# smart-home_matherboard.net
KiCad netlist of a schematic drawn in EAGLE
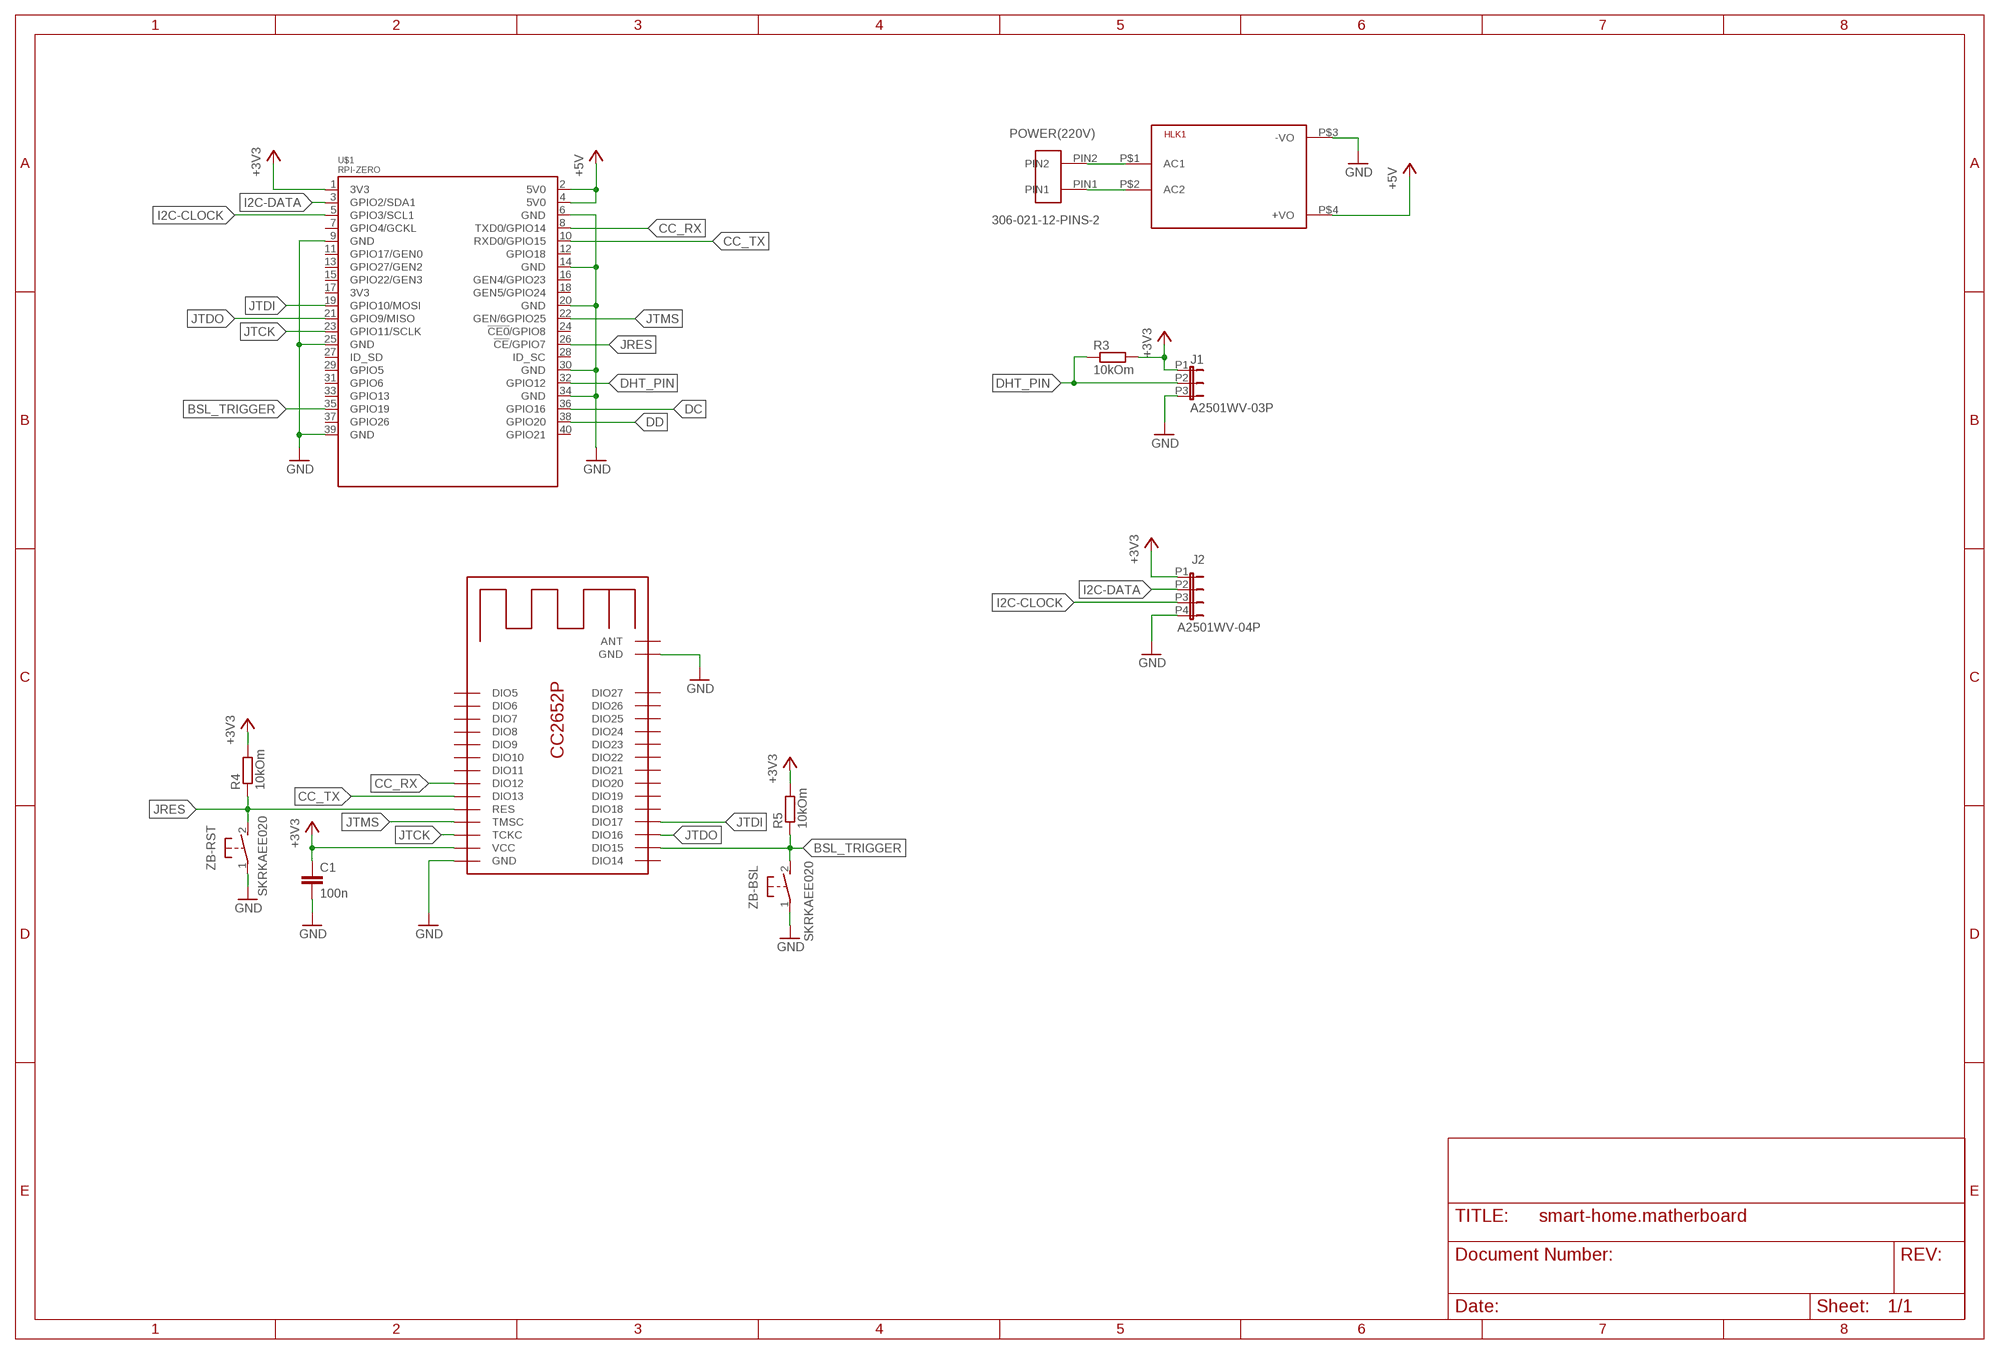
[diagram p0: schematic, sheet 1]

(export (version "E")
  (design (tool "Eeschema 10.0.6"))
  (components
    (comp (ref "C1")
      (value "100n")
      (footprint "eagle-import:C0603K")
      (libsource (lib "eagle-import") (part "C-EUC0603K"))
    )
    (comp (ref "HLK1")
      (value "HLK-PM013W")
      (footprint "eagle-import:HLK-PM01")
      (libsource (lib "eagle-import") (part "HLK-PM013W"))
    )
    (comp (ref "J1")
      (value "A2501WV-03P")
      (footprint "eagle-import:A2501WV-03P")
      (libsource (lib "eagle-import") (part "A2501WV-03P"))
    )
    (comp (ref "J2")
      (value "A2501WV-04P")
      (footprint "eagle-import:A2501WV-04P")
      (libsource (lib "eagle-import") (part "A2501WV-04P"))
    )
    (comp (ref "POWER(220V)")
      (value "306-021-12-PINS-2")
      (footprint "eagle-import:SERIA-306-2PIN")
      (libsource (lib "eagle-import") (part "306-021-12-PINS-2"))
    )
    (comp (ref "R3")
      (value "10kOm")
      (footprint "eagle-import:R0603")
      (libsource (lib "eagle-import") (part "R-EU_R0603"))
    )
    (comp (ref "R4")
      (value "10kOm")
      (footprint "eagle-import:R0603")
      (libsource (lib "eagle-import") (part "R-EU_R0603"))
    )
    (comp (ref "R5")
      (value "10kOm")
      (footprint "eagle-import:R0603")
      (libsource (lib "eagle-import") (part "R-EU_R0603"))
    )
    (comp (ref "U$1")
      (value "RPI-ZERO")
      (footprint "eagle-import:RASPBERRYPI_BASTELSTUBE_V13_RASPI_BOARD_B+_FULL")
      (libsource (lib "eagle-import") (part "RPI-ZERO"))
    )
    (comp (ref "U1")
      (value "CC2652P2-DUOWEISI")
      (footprint "eagle-import:CC2653P2-DUOWEISI")
      (libsource (lib "eagle-import") (part "CC2652P2-DUOWEISI"))
    )
    (comp (ref "ZB-BSL")
      (value "SKRKAEE020")
      (footprint "eagle-import:SKRKAEE020")
      (libsource (lib "eagle-import") (part "SKRKAEE020"))
    )
    (comp (ref "ZB-RST")
      (value "SKRKAEE020")
      (footprint "eagle-import:SKRKAEE020")
      (libsource (lib "eagle-import") (part "SKRKAEE020"))
    )
  )
  (nets
    (net (code "1") (name "+3V3") (class "Default")
      (node (ref "C1") (pin "1") (pinfunction "1_1") (pintype "passive"))
      (node (ref "J1") (pin "P1") (pinfunction "1_P1") (pintype "passive"))
      (node (ref "J2") (pin "P1") (pinfunction "1_P1") (pintype "passive"))
      (node (ref "R3") (pin "2") (pinfunction "2_2") (pintype "passive"))
      (node (ref "R4") (pin "2") (pinfunction "2_2") (pintype "passive"))
      (node (ref "R5") (pin "2") (pinfunction "2_2") (pintype "passive"))
      (node (ref "U$1") (pin "1") (pinfunction "3V3_1") (pintype "power_in"))
      (node (ref "U1") (pin "VCC") (pinfunction "VCC_VCC") (pintype "bidirectional"))
    )
    (net (code "2") (name "+5V") (class "Default")
      (node (ref "HLK1") (pin "P$4") (pinfunction "+VO_P$4") (pintype "bidirectional"))
      (node (ref "U$1") (pin "2") (pinfunction "5V0_2") (pintype "power_in"))
      (node (ref "U$1") (pin "4") (pinfunction "5V0_4") (pintype "power_in"))
    )
    (net (code "3") (name "/3V3") (class "Default")
      (node (ref "U$1") (pin "17") (pinfunction "3V3_17") (pintype "power_in"))
    )
    (net (code "4") (name "BSL_TRIGGER") (class "Default")
      (node (ref "R5") (pin "1") (pinfunction "1_1") (pintype "passive"))
      (node (ref "U$1") (pin "35") (pinfunction "GPIO19_35") (pintype "bidirectional"))
      (node (ref "U1") (pin "DIO15") (pinfunction "DIO15_DIO15") (pintype "bidirectional"))
      (node (ref "ZB-BSL") (pin "2") (pinfunction "2_2") (pintype "passive"))
    )
    (net (code "5") (name "CC_RX") (class "Default")
      (node (ref "U$1") (pin "8") (pinfunction "TXD0/GPIO14_8") (pintype "bidirectional"))
      (node (ref "U1") (pin "DIO12") (pinfunction "DIO12_DIO12") (pintype "bidirectional"))
    )
    (net (code "6") (name "CC_TX") (class "Default")
      (node (ref "U$1") (pin "10") (pinfunction "RXD0/GPIO15_10") (pintype "bidirectional"))
      (node (ref "U1") (pin "DIO13") (pinfunction "DIO13_DIO13") (pintype "bidirectional"))
    )
    (net (code "7") (name "DC") (class "Default")
      (node (ref "U$1") (pin "36") (pinfunction "GPIO16_36") (pintype "bidirectional"))
    )
    (net (code "8") (name "DD") (class "Default")
      (node (ref "U$1") (pin "38") (pinfunction "GPIO20_38") (pintype "bidirectional"))
    )
    (net (code "9") (name "DHT_PIN") (class "Default")
      (node (ref "J1") (pin "P2") (pinfunction "2_P2") (pintype "passive"))
      (node (ref "R3") (pin "1") (pinfunction "1_1") (pintype "passive"))
      (node (ref "U$1") (pin "32") (pinfunction "GPIO12_32") (pintype "bidirectional"))
    )
    (net (code "10") (name "GND") (class "Default")
      (node (ref "C1") (pin "2") (pinfunction "2_2") (pintype "passive"))
      (node (ref "HLK1") (pin "P$3") (pinfunction "-VO_P$3") (pintype "bidirectional"))
      (node (ref "J1") (pin "P3") (pinfunction "3_P3") (pintype "passive"))
      (node (ref "J2") (pin "P4") (pinfunction "4_P4") (pintype "passive"))
      (node (ref "U$1") (pin "14") (pinfunction "GND_14") (pintype "power_in"))
      (node (ref "U$1") (pin "20") (pinfunction "GND_20") (pintype "power_in"))
      (node (ref "U$1") (pin "25") (pinfunction "GND_25") (pintype "power_in"))
      (node (ref "U$1") (pin "30") (pinfunction "GND_30") (pintype "power_in"))
      (node (ref "U$1") (pin "34") (pinfunction "GND_34") (pintype "power_in"))
      (node (ref "U$1") (pin "39") (pinfunction "GND_39") (pintype "power_in"))
      (node (ref "U$1") (pin "6") (pinfunction "GND_6") (pintype "power_in"))
      (node (ref "U$1") (pin "9") (pinfunction "GND_9") (pintype "power_in"))
      (node (ref "U1") (pin "GND") (pinfunction "GND_GND") (pintype "bidirectional"))
      (node (ref "U1") (pin "GND@1") (pinfunction "GND_GND@1") (pintype "bidirectional"))
      (node (ref "ZB-BSL") (pin "1") (pinfunction "1_1") (pintype "passive"))
      (node (ref "ZB-RST") (pin "1") (pinfunction "1_1") (pintype "passive"))
    )
    (net (code "11") (name "I2C-CLOCK") (class "Default")
      (node (ref "J2") (pin "P3") (pinfunction "3_P3") (pintype "passive"))
      (node (ref "U$1") (pin "5") (pinfunction "GPIO3/SCL1_5") (pintype "bidirectional"))
    )
    (net (code "12") (name "I2C-DATA") (class "Default")
      (node (ref "J2") (pin "P2") (pinfunction "2_P2") (pintype "passive"))
      (node (ref "U$1") (pin "3") (pinfunction "GPIO2/SDA1_3") (pintype "bidirectional"))
    )
    (net (code "13") (name "JRES") (class "Default")
      (node (ref "R4") (pin "1") (pinfunction "1_1") (pintype "passive"))
      (node (ref "U$1") (pin "26") (pinfunction "~{CE}/GPIO7_26") (pintype "bidirectional"))
      (node (ref "U1") (pin "RES") (pinfunction "RES_RES") (pintype "bidirectional"))
      (node (ref "ZB-RST") (pin "2") (pinfunction "2_2") (pintype "passive"))
    )
    (net (code "14") (name "JTCK") (class "Default")
      (node (ref "U$1") (pin "23") (pinfunction "GPIO11/SCLK_23") (pintype "bidirectional"))
      (node (ref "U1") (pin "TCKC") (pinfunction "TCKC_TCKC") (pintype "bidirectional"))
    )
    (net (code "15") (name "JTDI") (class "Default")
      (node (ref "U$1") (pin "19") (pinfunction "GPIO10/MOSI_19") (pintype "bidirectional"))
      (node (ref "U1") (pin "DIO17") (pinfunction "DIO17_DIO17") (pintype "bidirectional"))
    )
    (net (code "16") (name "JTDO") (class "Default")
      (node (ref "U$1") (pin "21") (pinfunction "GPIO9/MISO_21") (pintype "bidirectional"))
      (node (ref "U1") (pin "DIO16") (pinfunction "DIO16_DIO16") (pintype "bidirectional"))
    )
    (net (code "17") (name "JTMS") (class "Default")
      (node (ref "U$1") (pin "22") (pinfunction "GEN/6GPIO25_22") (pintype "bidirectional"))
      (node (ref "U1") (pin "TMSC") (pinfunction "TMSC_TMSC") (pintype "bidirectional"))
    )
    (net (code "18") (name "Net-(HLK1-AC1)") (class "Default")
      (node (ref "HLK1") (pin "P$1") (pinfunction "AC1_P$1") (pintype "bidirectional"))
      (node (ref "POWER(220V)") (pin "PIN2") (pinfunction "PIN2_PIN2") (pintype "bidirectional"))
    )
    (net (code "19") (name "Net-(HLK1-AC2)") (class "Default")
      (node (ref "HLK1") (pin "P$2") (pinfunction "AC2_P$2") (pintype "bidirectional"))
      (node (ref "POWER(220V)") (pin "PIN1") (pinfunction "PIN1_PIN1") (pintype "bidirectional"))
    )
    (net (code "20") (name "unconnected-(U$1-GEN4{slash}GPIO23-Pad16)") (class "Default")
      (node (ref "U$1") (pin "16") (pinfunction "GEN4/GPIO23_16") (pintype "bidirectional"))
    )
    (net (code "21") (name "unconnected-(U$1-GEN5{slash}GPIO24-Pad18)") (class "Default")
      (node (ref "U$1") (pin "18") (pinfunction "GEN5/GPIO24_18") (pintype "bidirectional"))
    )
    (net (code "22") (name "unconnected-(U$1-GPIO4{slash}GCKL-Pad7)") (class "Default")
      (node (ref "U$1") (pin "7") (pinfunction "GPIO4/GCKL_7") (pintype "bidirectional"))
    )
    (net (code "23") (name "unconnected-(U$1-GPIO5-Pad29)") (class "Default")
      (node (ref "U$1") (pin "29") (pinfunction "GPIO5_29") (pintype "bidirectional"))
    )
    (net (code "24") (name "unconnected-(U$1-GPIO6-Pad31)") (class "Default")
      (node (ref "U$1") (pin "31") (pinfunction "GPIO6_31") (pintype "bidirectional"))
    )
    (net (code "25") (name "unconnected-(U$1-GPIO13-Pad33)") (class "Default")
      (node (ref "U$1") (pin "33") (pinfunction "GPIO13_33") (pintype "bidirectional"))
    )
    (net (code "26") (name "unconnected-(U$1-GPIO17{slash}GEN0-Pad11)") (class "Default")
      (node (ref "U$1") (pin "11") (pinfunction "GPIO17/GEN0_11") (pintype "bidirectional"))
    )
    (net (code "27") (name "unconnected-(U$1-GPIO18-Pad12)") (class "Default")
      (node (ref "U$1") (pin "12") (pinfunction "GPIO18_12") (pintype "bidirectional"))
    )
    (net (code "28") (name "unconnected-(U$1-GPIO21-Pad40)") (class "Default")
      (node (ref "U$1") (pin "40") (pinfunction "GPIO21_40") (pintype "bidirectional"))
    )
    (net (code "29") (name "unconnected-(U$1-GPIO22{slash}GEN3-Pad15)") (class "Default")
      (node (ref "U$1") (pin "15") (pinfunction "GPIO22/GEN3_15") (pintype "bidirectional"))
    )
    (net (code "30") (name "unconnected-(U$1-GPIO26-Pad37)") (class "Default")
      (node (ref "U$1") (pin "37") (pinfunction "GPIO26_37") (pintype "bidirectional"))
    )
    (net (code "31") (name "unconnected-(U$1-GPIO27{slash}GEN2-Pad13)") (class "Default")
      (node (ref "U$1") (pin "13") (pinfunction "GPIO27/GEN2_13") (pintype "bidirectional"))
    )
    (net (code "32") (name "unconnected-(U$1-ID_SC-Pad28)") (class "Default")
      (node (ref "U$1") (pin "28") (pinfunction "ID_SC_28") (pintype "bidirectional"))
    )
    (net (code "33") (name "unconnected-(U$1-ID_SD-Pad27)") (class "Default")
      (node (ref "U$1") (pin "27") (pinfunction "ID_SD_27") (pintype "bidirectional"))
    )
    (net (code "34") (name "unconnected-(U$1-~{CE0}{slash}GPIO8-Pad24)") (class "Default")
      (node (ref "U$1") (pin "24") (pinfunction "~{CE0}/GPIO8_24") (pintype "bidirectional"))
    )
    (net (code "35") (name "unconnected-(U1-PadANT)") (class "Default")
      (node (ref "U1") (pin "ANT") (pinfunction "ANT_ANT") (pintype "bidirectional"))
    )
    (net (code "36") (name "unconnected-(U1-PadDIO5)") (class "Default")
      (node (ref "U1") (pin "DIO5") (pinfunction "DIO5_DIO5") (pintype "bidirectional"))
    )
    (net (code "37") (name "unconnected-(U1-PadDIO6)") (class "Default")
      (node (ref "U1") (pin "DIO6") (pinfunction "DIO6_DIO6") (pintype "bidirectional"))
    )
    (net (code "38") (name "unconnected-(U1-PadDIO7)") (class "Default")
      (node (ref "U1") (pin "DIO7") (pinfunction "DIO7_DIO7") (pintype "bidirectional"))
    )
    (net (code "39") (name "unconnected-(U1-PadDIO8)") (class "Default")
      (node (ref "U1") (pin "DIO8") (pinfunction "DIO8_DIO8") (pintype "bidirectional"))
    )
    (net (code "40") (name "unconnected-(U1-PadDIO9)") (class "Default")
      (node (ref "U1") (pin "DIO9") (pinfunction "DIO9_DIO9") (pintype "bidirectional"))
    )
    (net (code "41") (name "unconnected-(U1-PadDIO10)") (class "Default")
      (node (ref "U1") (pin "DIO10") (pinfunction "DIO10_DIO10") (pintype "bidirectional"))
    )
    (net (code "42") (name "unconnected-(U1-PadDIO11)") (class "Default")
      (node (ref "U1") (pin "DIO11") (pinfunction "DIO11_DIO11") (pintype "bidirectional"))
    )
    (net (code "43") (name "unconnected-(U1-PadDIO14)") (class "Default")
      (node (ref "U1") (pin "DIO14") (pinfunction "DIO14_DIO14") (pintype "bidirectional"))
    )
    (net (code "44") (name "unconnected-(U1-PadDIO18)") (class "Default")
      (node (ref "U1") (pin "DIO18") (pinfunction "DIO18_DIO18") (pintype "bidirectional"))
    )
    (net (code "45") (name "unconnected-(U1-PadDIO19)") (class "Default")
      (node (ref "U1") (pin "DIO19") (pinfunction "DIO19_DIO19") (pintype "bidirectional"))
    )
    (net (code "46") (name "unconnected-(U1-PadDIO20)") (class "Default")
      (node (ref "U1") (pin "DIO20") (pinfunction "DIO20_DIO20") (pintype "bidirectional"))
    )
    (net (code "47") (name "unconnected-(U1-PadDIO21)") (class "Default")
      (node (ref "U1") (pin "DIO21") (pinfunction "DIO21_DIO21") (pintype "bidirectional"))
    )
    (net (code "48") (name "unconnected-(U1-PadDIO22)") (class "Default")
      (node (ref "U1") (pin "DIO22") (pinfunction "DIO22_DIO22") (pintype "bidirectional"))
    )
    (net (code "49") (name "unconnected-(U1-PadDIO23)") (class "Default")
      (node (ref "U1") (pin "DIO23") (pinfunction "DIO23_DIO23") (pintype "bidirectional"))
    )
    (net (code "50") (name "unconnected-(U1-PadDIO24)") (class "Default")
      (node (ref "U1") (pin "DIO24") (pinfunction "DIO24_DIO24") (pintype "bidirectional"))
    )
    (net (code "51") (name "unconnected-(U1-PadDIO25)") (class "Default")
      (node (ref "U1") (pin "DIO25") (pinfunction "DIO25_DIO25") (pintype "bidirectional"))
    )
    (net (code "52") (name "unconnected-(U1-PadDIO26)") (class "Default")
      (node (ref "U1") (pin "DIO26") (pinfunction "DIO26_DIO26") (pintype "bidirectional"))
    )
    (net (code "53") (name "unconnected-(U1-PadDIO27)") (class "Default")
      (node (ref "U1") (pin "DIO27") (pinfunction "DIO27_DIO27") (pintype "bidirectional"))
    )
  )
)
